# EasyEDA_Source.net
KiCad netlist of a schematic drawn in EasyEDA
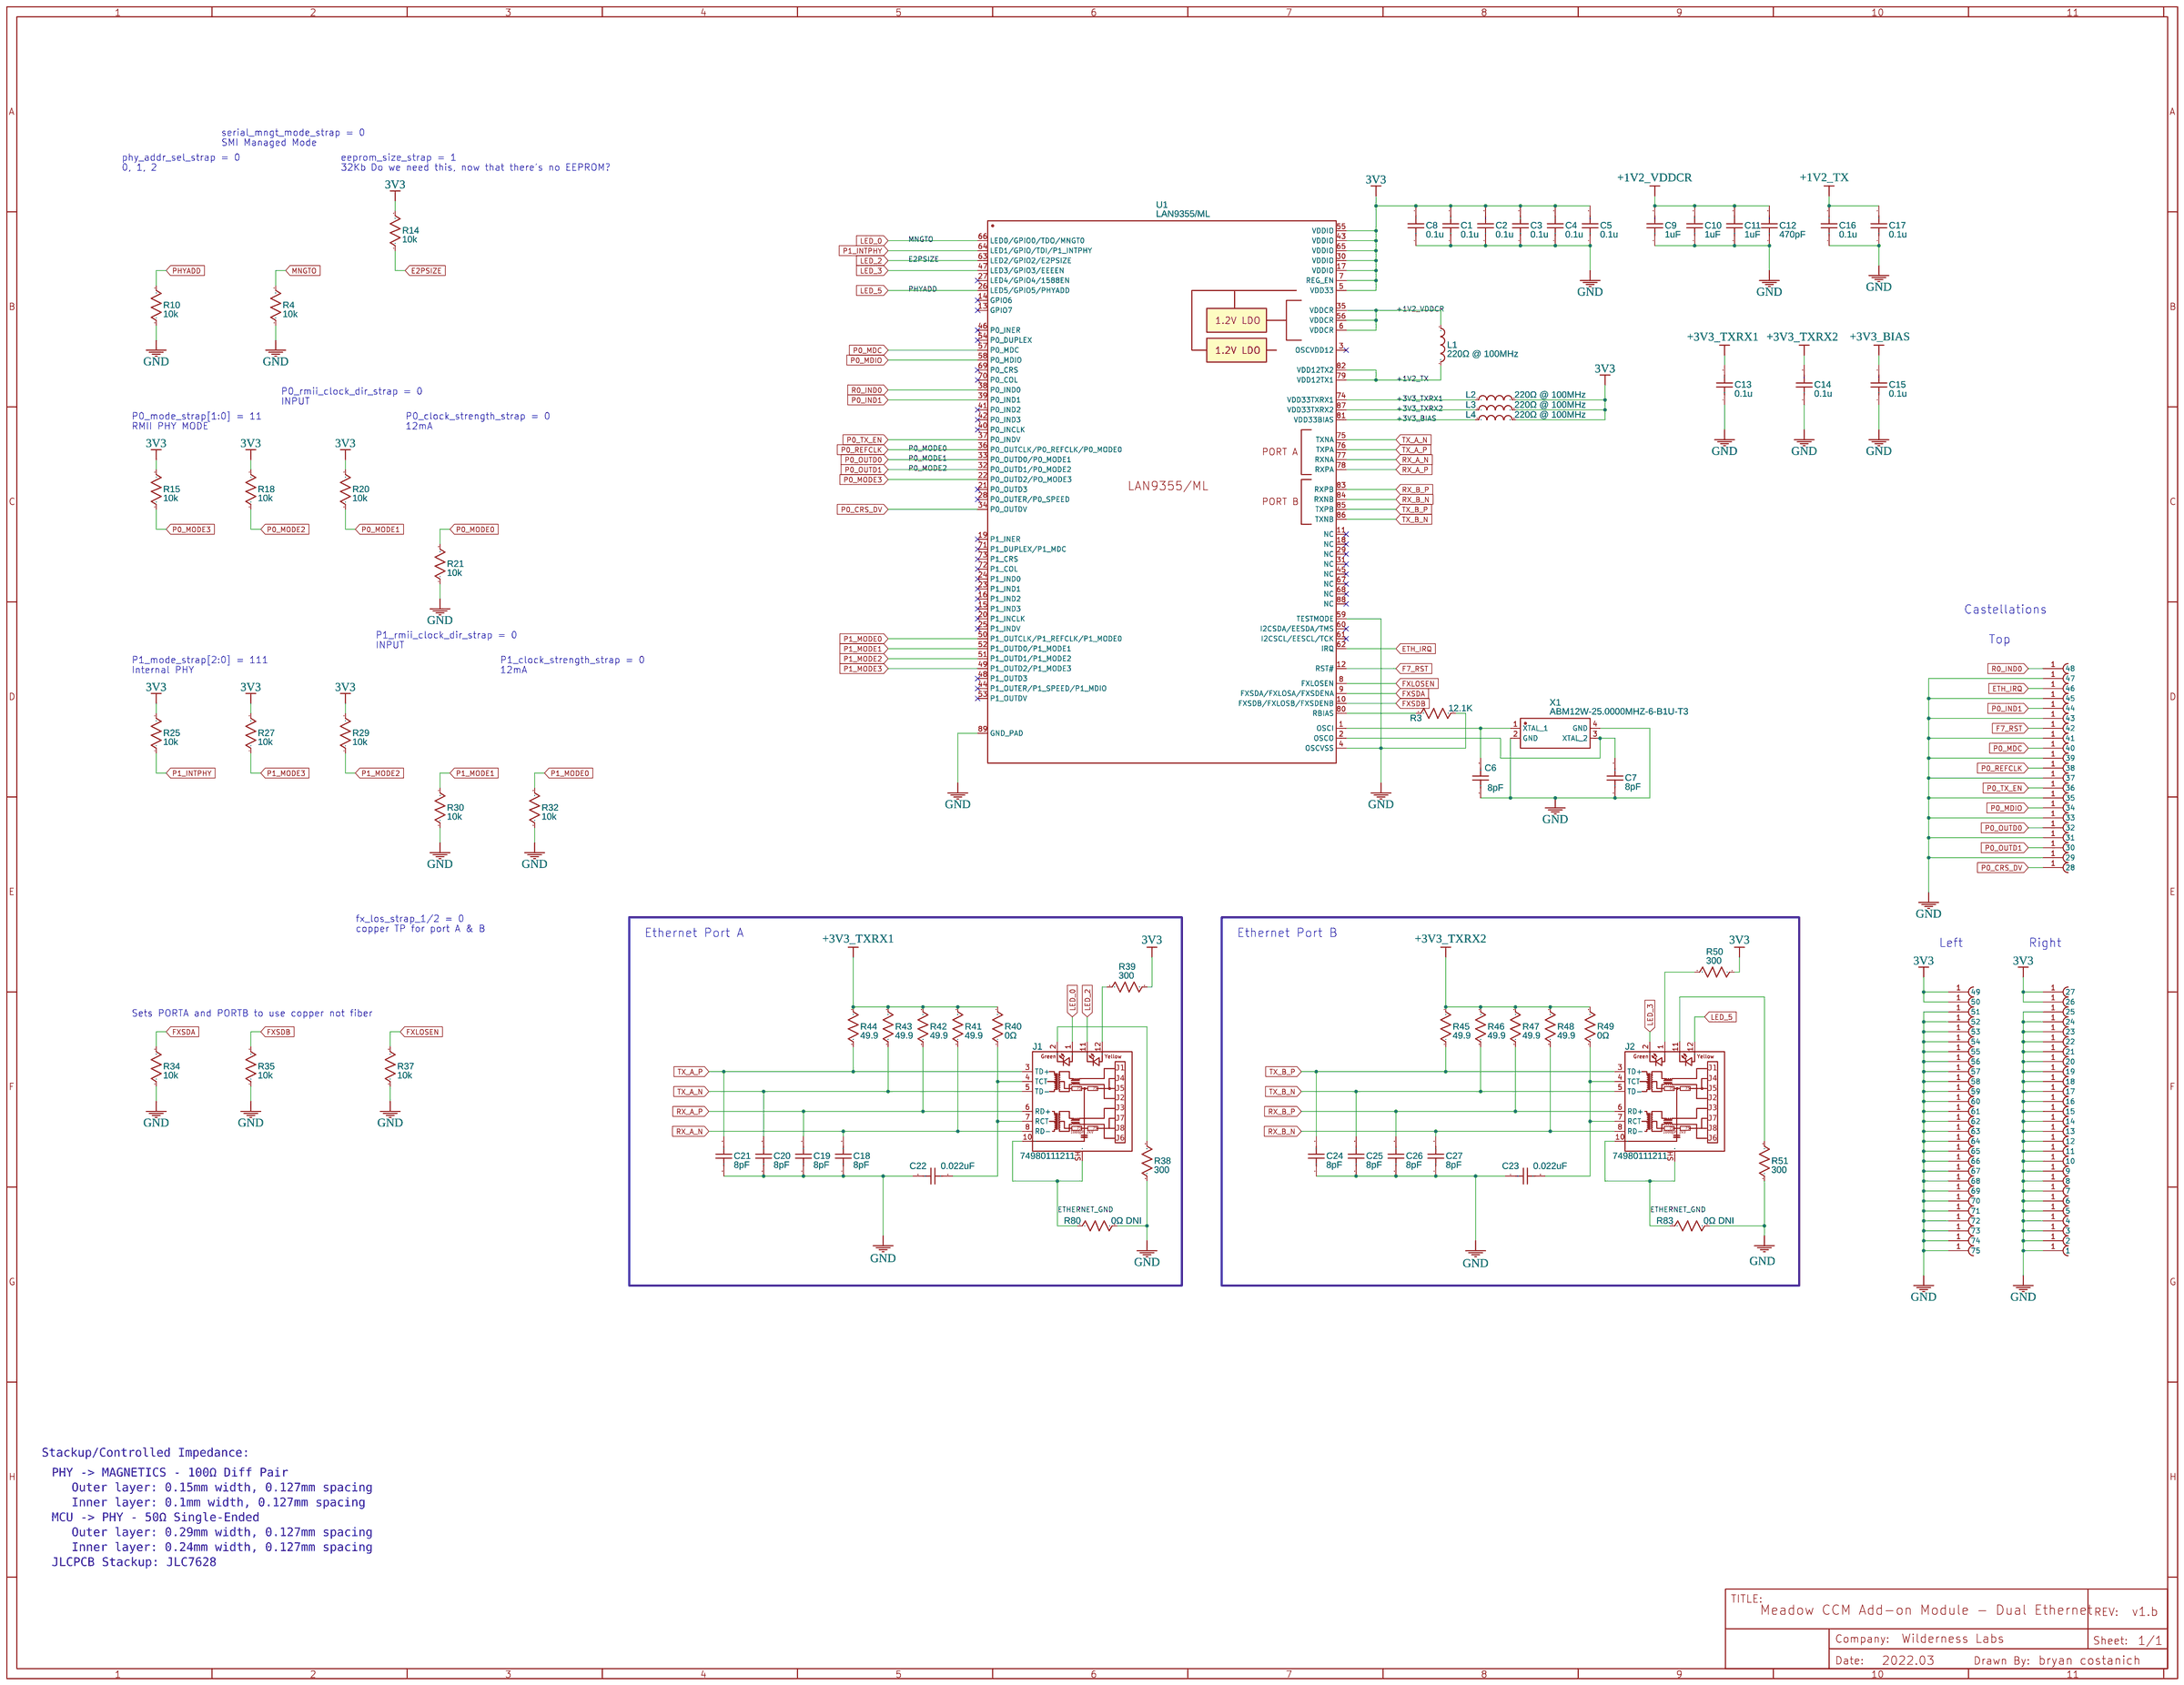
[diagram p0: schematic sheet]

(export (version "E")
  (design (tool "Eeschema 10.0.6"))
  (components
    (comp (ref "C1")
      (value "0.1u")
      (fields (field (name "BOM_Manufacturer Part") "CC0603KRX7R7BB104"))
      (libsource (lib "") (part "C_0603_US"))
    )
    (comp (ref "C2")
      (value "0.1u")
      (fields (field (name "BOM_Manufacturer Part") "CC0603KRX7R7BB104"))
      (libsource (lib "") (part "C_0603_US"))
    )
    (comp (ref "C3")
      (value "0.1u")
      (fields (field (name "BOM_Manufacturer Part") "CC0603KRX7R7BB104"))
      (libsource (lib "") (part "C_0603_US"))
    )
    (comp (ref "C4")
      (value "0.1u")
      (fields (field (name "BOM_Manufacturer Part") "CC0603KRX7R7BB104"))
      (libsource (lib "") (part "C_0603_US"))
    )
    (comp (ref "C5")
      (value "0.1u")
      (fields (field (name "BOM_Manufacturer Part") "CC0603KRX7R7BB104"))
      (libsource (lib "") (part "C_0603_US"))
    )
    (comp (ref "C6")
      (value "8pF")
      (fields (field (name "BOM_Manufacturer Part") "CC0603DRNPO9BN8R0"))
      (libsource (lib "") (part "C_0603_US"))
    )
    (comp (ref "C7")
      (value "8pF")
      (fields (field (name "BOM_Manufacturer Part") "CC0603DRNPO9BN8R0"))
      (libsource (lib "") (part "C_0603_US"))
    )
    (comp (ref "C8")
      (value "0.1u")
      (fields (field (name "BOM_Manufacturer Part") "CC0603KRX7R7BB104"))
      (libsource (lib "") (part "C_0603_US"))
    )
    (comp (ref "C9")
      (value "1uF")
      (fields (field (name "BOM_Manufacturer Part") "CC0603ZRY5V6BB105"))
      (libsource (lib "") (part "C_0603_US"))
    )
    (comp (ref "C10")
      (value "1uF")
      (fields (field (name "BOM_Manufacturer Part") "CC0603ZRY5V6BB105"))
      (libsource (lib "") (part "C_0603_US"))
    )
    (comp (ref "C11")
      (value "1uF")
      (fields (field (name "BOM_Manufacturer Part") "CC0603ZRY5V6BB105"))
      (libsource (lib "") (part "C_0603_US"))
    )
    (comp (ref "C12")
      (value "470pF")
      (fields (field (name "BOM_Manufacturer Part") "CC0603KRX7R9BB471"))
      (libsource (lib "") (part "C_0603_US"))
    )
    (comp (ref "C13")
      (value "0.1u")
      (fields (field (name "BOM_Manufacturer Part") "CC0603KRX7R7BB104"))
      (libsource (lib "") (part "C_0603_US"))
    )
    (comp (ref "C14")
      (value "0.1u")
      (fields (field (name "BOM_Manufacturer Part") "CC0603KRX7R7BB104"))
      (libsource (lib "") (part "C_0603_US"))
    )
    (comp (ref "C15")
      (value "0.1u")
      (fields (field (name "BOM_Manufacturer Part") "CC0603KRX7R7BB104"))
      (libsource (lib "") (part "C_0603_US"))
    )
    (comp (ref "C16")
      (value "0.1u")
      (fields (field (name "BOM_Manufacturer Part") "CC0603KRX7R7BB104"))
      (libsource (lib "") (part "C_0603_US"))
    )
    (comp (ref "C17")
      (value "0.1u")
      (fields (field (name "BOM_Manufacturer Part") "CC0603KRX7R7BB104"))
      (libsource (lib "") (part "C_0603_US"))
    )
    (comp (ref "C18")
      (value "8pF")
      (fields (field (name "BOM_Manufacturer Part") "CC0603DRNPO9BN8R0"))
      (libsource (lib "") (part "C_0603_US"))
    )
    (comp (ref "C19")
      (value "8pF")
      (fields (field (name "BOM_Manufacturer Part") "CC0603DRNPO9BN8R0"))
      (libsource (lib "") (part "C_0603_US"))
    )
    (comp (ref "C20")
      (value "8pF")
      (fields (field (name "BOM_Manufacturer Part") "CC0603DRNPO9BN8R0"))
      (libsource (lib "") (part "C_0603_US"))
    )
    (comp (ref "C21")
      (value "8pF")
      (fields (field (name "BOM_Manufacturer Part") "CC0603DRNPO9BN8R0"))
      (libsource (lib "") (part "C_0603_US"))
    )
    (comp (ref "C22")
      (value "0.022uF")
      (fields (field (name "BOM_Manufacturer Part") "CC0603KRX7R8BB223"))
      (libsource (lib "") (part "C_0603_US_1"))
    )
    (comp (ref "C23")
      (value "0.022uF")
      (fields (field (name "BOM_Manufacturer Part") "CC0603KRX7R8BB223"))
      (libsource (lib "") (part "C_0603_US_1"))
    )
    (comp (ref "C24")
      (value "8pF")
      (fields (field (name "BOM_Manufacturer Part") "CC0603DRNPO9BN8R0"))
      (libsource (lib "") (part "C_0603_US"))
    )
    (comp (ref "C25")
      (value "8pF")
      (fields (field (name "BOM_Manufacturer Part") "CC0603DRNPO9BN8R0"))
      (libsource (lib "") (part "C_0603_US"))
    )
    (comp (ref "C26")
      (value "8pF")
      (fields (field (name "BOM_Manufacturer Part") "CC0603DRNPO9BN8R0"))
      (libsource (lib "") (part "C_0603_US"))
    )
    (comp (ref "C27")
      (value "8pF")
      (fields (field (name "BOM_Manufacturer Part") "CC0603DRNPO9BN8R0"))
      (libsource (lib "") (part "C_0603_US"))
    )
    (comp (ref "J1") (value "74980111211") (libsource (lib "") (part "74980111211")))
    (comp (ref "J2") (value "74980111211") (libsource (lib "") (part "74980111211")))
    (comp (ref "L1")
      (value "220Ω @ 100MHz")
      (fields (field (name "BOM_Manufacturer Part") "BLM18KG221SN1D"))
      (libsource (lib "") (part "L0603_US_1"))
    )
    (comp (ref "L2")
      (value "220Ω @ 100MHz")
      (fields (field (name "BOM_Manufacturer Part") "BLM18KG221SN1D"))
      (libsource (lib "") (part "L0603_US"))
    )
    (comp (ref "L3")
      (value "220Ω @ 100MHz")
      (fields (field (name "BOM_Manufacturer Part") "BLM18KG221SN1D"))
      (libsource (lib "") (part "L0603_US"))
    )
    (comp (ref "L4")
      (value "220Ω @ 100MHz")
      (fields (field (name "BOM_Manufacturer Part") "BLM18KG221SN1D"))
      (libsource (lib "") (part "L0603_US"))
    )
    (comp (ref "R3")
      (value "12.1K")
      (fields (field (name "BOM_Manufacturer Part") "RC0603FR-0712K1L"))
      (libsource (lib "") (part "R_0603_US_1"))
    )
    (comp (ref "R4")
      (value "10k")
      (fields (field (name "BOM_Manufacturer Part") "RC0603FR-0710KL"))
      (libsource (lib "") (part "R_0603_US"))
    )
    (comp (ref "R10")
      (value "10k")
      (fields (field (name "BOM_Manufacturer Part") "RC0603FR-0710KL"))
      (libsource (lib "") (part "R_0603_US"))
    )
    (comp (ref "R14")
      (value "10k")
      (fields (field (name "BOM_Manufacturer Part") "RC0603FR-0710KL"))
      (libsource (lib "") (part "R_0603_US"))
    )
    (comp (ref "R15")
      (value "10k")
      (fields (field (name "BOM_Manufacturer Part") "RC0603FR-0710KL"))
      (libsource (lib "") (part "R_0603_US"))
    )
    (comp (ref "R18")
      (value "10k")
      (fields (field (name "BOM_Manufacturer Part") "RC0603FR-0710KL"))
      (libsource (lib "") (part "R_0603_US"))
    )
    (comp (ref "R20")
      (value "10k")
      (fields (field (name "BOM_Manufacturer Part") "RC0603FR-0710KL"))
      (libsource (lib "") (part "R_0603_US"))
    )
    (comp (ref "R21")
      (value "10k")
      (fields (field (name "BOM_Manufacturer Part") "RC0603FR-0710KL"))
      (libsource (lib "") (part "R_0603_US"))
    )
    (comp (ref "R25")
      (value "10k")
      (fields (field (name "BOM_Manufacturer Part") "RC0603FR-0710KL"))
      (libsource (lib "") (part "R_0603_US"))
    )
    (comp (ref "R27")
      (value "10k")
      (fields (field (name "BOM_Manufacturer Part") "RC0603FR-0710KL"))
      (libsource (lib "") (part "R_0603_US"))
    )
    (comp (ref "R29")
      (value "10k")
      (fields (field (name "BOM_Manufacturer Part") "RC0603FR-0710KL"))
      (libsource (lib "") (part "R_0603_US"))
    )
    (comp (ref "R30")
      (value "10k")
      (fields (field (name "BOM_Manufacturer Part") "RC0603FR-0710KL"))
      (libsource (lib "") (part "R_0603_US"))
    )
    (comp (ref "R32")
      (value "10k")
      (fields (field (name "BOM_Manufacturer Part") "RC0603FR-0710KL"))
      (libsource (lib "") (part "R_0603_US"))
    )
    (comp (ref "R34")
      (value "10k")
      (fields (field (name "BOM_Manufacturer Part") "RC0603FR-0710KL"))
      (libsource (lib "") (part "R_0603_US"))
    )
    (comp (ref "R35")
      (value "10k")
      (fields (field (name "BOM_Manufacturer Part") "RC0603FR-0710KL"))
      (libsource (lib "") (part "R_0603_US"))
    )
    (comp (ref "R37")
      (value "10k")
      (fields (field (name "BOM_Manufacturer Part") "RC0603FR-0710KL"))
      (libsource (lib "") (part "R_0603_US"))
    )
    (comp (ref "R38")
      (value "300")
      (fields (field (name "BOM_Manufacturer Part") "RC0603FR-07300RL"))
      (libsource (lib "") (part "R_0603_US"))
    )
    (comp (ref "R39")
      (value "300")
      (fields (field (name "BOM_Manufacturer Part") "RC0603FR-07300RL"))
      (libsource (lib "") (part "R_0603_US_1"))
    )
    (comp (ref "R40")
      (value "0Ω")
      (fields (field (name "BOM_Manufacturer Part") "RC0603JR-070RL"))
      (libsource (lib "") (part "R_0603_US"))
    )
    (comp (ref "R41")
      (value "49.9")
      (fields (field (name "BOM_Manufacturer Part") "RC0603FR-0749R9L"))
      (libsource (lib "") (part "R_0603_US"))
    )
    (comp (ref "R42")
      (value "49.9")
      (fields (field (name "BOM_Manufacturer Part") "RC0603FR-0749R9L"))
      (libsource (lib "") (part "R_0603_US"))
    )
    (comp (ref "R43")
      (value "49.9")
      (fields (field (name "BOM_Manufacturer Part") "RC0603FR-0749R9L"))
      (libsource (lib "") (part "R_0603_US"))
    )
    (comp (ref "R44")
      (value "49.9")
      (fields (field (name "BOM_Manufacturer Part") "RC0603FR-0749R9L"))
      (libsource (lib "") (part "R_0603_US"))
    )
    (comp (ref "R45")
      (value "49.9")
      (fields (field (name "BOM_Manufacturer Part") "RC0603FR-0749R9L"))
      (libsource (lib "") (part "R_0603_US"))
    )
    (comp (ref "R46")
      (value "49.9")
      (fields (field (name "BOM_Manufacturer Part") "RC0603FR-0749R9L"))
      (libsource (lib "") (part "R_0603_US"))
    )
    (comp (ref "R47")
      (value "49.9")
      (fields (field (name "BOM_Manufacturer Part") "RC0603FR-0749R9L"))
      (libsource (lib "") (part "R_0603_US"))
    )
    (comp (ref "R48")
      (value "49.9")
      (fields (field (name "BOM_Manufacturer Part") "RC0603FR-0749R9L"))
      (libsource (lib "") (part "R_0603_US"))
    )
    (comp (ref "R49")
      (value "0Ω")
      (fields (field (name "BOM_Manufacturer Part") "RC0603JR-070RL"))
      (libsource (lib "") (part "R_0603_US"))
    )
    (comp (ref "R50")
      (value "300")
      (fields (field (name "BOM_Manufacturer Part") "RC0603FR-07300RL"))
      (libsource (lib "") (part "R_0603_US_1"))
    )
    (comp (ref "R51")
      (value "300")
      (fields (field (name "BOM_Manufacturer Part") "RC0603FR-07300RL"))
      (libsource (lib "") (part "R_0603_US"))
    )
    (comp (ref "R80")
      (value "0Ω DNI")
      (fields (field (name "BOM_Manufacturer Part") "RC0603JR-070RL"))
      (libsource (lib "") (part "R_0603_US_2"))
    )
    (comp (ref "R83")
      (value "0Ω DNI")
      (fields (field (name "BOM_Manufacturer Part") "RC0603JR-070RL"))
      (libsource (lib "") (part "R_0603_US_2"))
    )
    (comp (ref "U1")
      (value "LAN9355/ML")
      (fields (field (name "BOM_Manufacturer Part") "LAN9355I/ML"))
      (libsource (lib "") (part "LAN9355/ML"))
    )
    (comp (ref "U2") (value "1.2MM SMT Castellation") (libsource (lib "") (part "1.2MM SMT Castellation_69")))
    (comp (ref "U3") (value "1.2MM SMT Castellation") (libsource (lib "") (part "1.2MM SMT Castellation_27")))
    (comp (ref "U4") (value "1.2MM SMT Castellation") (libsource (lib "") (part "1.2MM SMT Castellation_32")))
    (comp (ref "U5") (value "1.2MM SMT Castellation") (libsource (lib "") (part "1.2MM SMT Castellation_5")))
    (comp (ref "U6") (value "1.2MM SMT Castellation") (libsource (lib "") (part "1.2MM SMT Castellation_40")))
    (comp (ref "U7") (value "1.2MM SMT Castellation") (libsource (lib "") (part "1.2MM SMT Castellation_8")))
    (comp (ref "U8") (value "1.2MM SMT Castellation") (libsource (lib "") (part "1.2MM SMT Castellation_25")))
    (comp (ref "U9") (value "1.2MM SMT Castellation") (libsource (lib "") (part "1.2MM SMT Castellation_70")))
    (comp (ref "U10")
      (value "1.2MM SMT Castellation")
      (libsource (lib "") (part "1.2MM SMT Castellation_12"))
    )
    (comp (ref "U11")
      (value "1.2MM SMT Castellation")
      (libsource (lib "") (part "1.2MM SMT Castellation_68"))
    )
    (comp (ref "U12")
      (value "WILDERNESS_LABS_LOGO_HORIZONTAL_MEDIUM")
      (libsource (lib "") (part "WILDERNESS_LABS_LOGO_HORIZONTAL_MEDIUM"))
    )
    (comp (ref "U13")
      (value "1.2MM SMT Castellation")
      (libsource (lib "") (part "1.2MM SMT Castellation_34"))
    )
    (comp (ref "U14") (value "1.2MM SMT Castellation") (libsource (lib "") (part "1.2MM SMT Castellation_6")))
    (comp (ref "U15")
      (value "1.2MM SMT Castellation")
      (libsource (lib "") (part "1.2MM SMT Castellation_21"))
    )
    (comp (ref "U16")
      (value "1.2MM SMT Castellation")
      (libsource (lib "") (part "1.2MM SMT Castellation_43"))
    )
    (comp (ref "U17")
      (value "1.2MM SMT Castellation")
      (libsource (lib "") (part "1.2MM SMT Castellation_30"))
    )
    (comp (ref "U18")
      (value "1.2MM SMT Castellation")
      (libsource (lib "") (part "1.2MM SMT Castellation_41"))
    )
    (comp (ref "U19")
      (value "1.2MM SMT Castellation")
      (libsource (lib "") (part "1.2MM SMT Castellation_10"))
    )
    (comp (ref "U20")
      (value "1.2MM SMT Castellation")
      (libsource (lib "") (part "1.2MM SMT Castellation_19"))
    )
    (comp (ref "U21")
      (value "1.2MM SMT Castellation")
      (libsource (lib "") (part "1.2MM SMT Castellation_37"))
    )
    (comp (ref "U22")
      (value "1.2MM SMT Castellation")
      (libsource (lib "") (part "1.2MM SMT Castellation_42"))
    )
    (comp (ref "U23")
      (value "1.2MM SMT Castellation")
      (libsource (lib "") (part "1.2MM SMT Castellation_11"))
    )
    (comp (ref "U24")
      (value "1.2MM SMT Castellation")
      (libsource (lib "") (part "1.2MM SMT Castellation_60"))
    )
    (comp (ref "U25")
      (value "1.2MM SMT Castellation")
      (libsource (lib "") (part "1.2MM SMT Castellation_46"))
    )
    (comp (ref "U26")
      (value "1.2MM SMT Castellation")
      (libsource (lib "") (part "1.2MM SMT Castellation_57"))
    )
    (comp (ref "U27")
      (value "1.2MM SMT Castellation")
      (libsource (lib "") (part "1.2MM SMT Castellation_63"))
    )
    (comp (ref "U28")
      (value "1.2MM SMT Castellation")
      (libsource (lib "") (part "1.2MM SMT Castellation_38"))
    )
    (comp (ref "U29")
      (value "1.2MM SMT Castellation")
      (libsource (lib "") (part "1.2MM SMT Castellation_48"))
    )
    (comp (ref "U30")
      (value "1.2MM SMT Castellation")
      (libsource (lib "") (part "1.2MM SMT Castellation_62"))
    )
    (comp (ref "U31")
      (value "1.2MM SMT Castellation")
      (libsource (lib "") (part "1.2MM SMT Castellation_23"))
    )
    (comp (ref "U32")
      (value "1.2MM SMT Castellation")
      (libsource (lib "") (part "1.2MM SMT Castellation_55"))
    )
    (comp (ref "U33")
      (value "1.2MM SMT Castellation")
      (libsource (lib "") (part "1.2MM SMT Castellation_65"))
    )
    (comp (ref "U34")
      (value "1.2MM SMT Castellation")
      (libsource (lib "") (part "1.2MM SMT Castellation_67"))
    )
    (comp (ref "U35")
      (value "1.2MM SMT Castellation")
      (libsource (lib "") (part "1.2MM SMT Castellation_72"))
    )
    (comp (ref "U36")
      (value "1.2MM SMT Castellation")
      (libsource (lib "") (part "1.2MM SMT Castellation_47"))
    )
    (comp (ref "U37")
      (value "1.2MM SMT Castellation")
      (libsource (lib "") (part "1.2MM SMT Castellation_20"))
    )
    (comp (ref "U38")
      (value "1.2MM SMT Castellation")
      (libsource (lib "") (part "1.2MM SMT Castellation_51"))
    )
    (comp (ref "U39")
      (value "1.2MM SMT Castellation")
      (libsource (lib "") (part "1.2MM SMT Castellation_24"))
    )
    (comp (ref "U40")
      (value "1.2MM SMT Castellation")
      (libsource (lib "") (part "1.2MM SMT Castellation_56"))
    )
    (comp (ref "U41")
      (value "1.2MM SMT Castellation")
      (libsource (lib "") (part "1.2MM SMT Castellation_36"))
    )
    (comp (ref "U42")
      (value "1.2MM SMT Castellation")
      (libsource (lib "") (part "1.2MM SMT Castellation_22"))
    )
    (comp (ref "U43")
      (value "1.2MM SMT Castellation")
      (libsource (lib "") (part "1.2MM SMT Castellation_73"))
    )
    (comp (ref "U44")
      (value "1.2MM SMT Castellation")
      (libsource (lib "") (part "1.2MM SMT Castellation_39"))
    )
    (comp (ref "U45")
      (value "1.2MM SMT Castellation")
      (libsource (lib "") (part "1.2MM SMT Castellation_52"))
    )
    (comp (ref "U46")
      (value "1.2MM SMT Castellation")
      (libsource (lib "") (part "1.2MM SMT Castellation_33"))
    )
    (comp (ref "U47") (value "1.2MM SMT Castellation") (libsource (lib "") (part "1.2MM SMT Castellation")))
    (comp (ref "U48")
      (value "1.2MM SMT Castellation")
      (libsource (lib "") (part "1.2MM SMT Castellation_18"))
    )
    (comp (ref "U49")
      (value "1.2MM SMT Castellation")
      (libsource (lib "") (part "1.2MM SMT Castellation_50"))
    )
    (comp (ref "U50")
      (value "1.2MM SMT Castellation")
      (libsource (lib "") (part "1.2MM SMT Castellation_49"))
    )
    (comp (ref "U51")
      (value "1.2MM SMT Castellation")
      (libsource (lib "") (part "1.2MM SMT Castellation_15"))
    )
    (comp (ref "U52")
      (value "1.2MM SMT Castellation")
      (libsource (lib "") (part "1.2MM SMT Castellation_64"))
    )
    (comp (ref "U53") (value "1.2MM SMT Castellation") (libsource (lib "") (part "1.2MM SMT Castellation_7")))
    (comp (ref "U54")
      (value "1.2MM SMT Castellation")
      (libsource (lib "") (part "1.2MM SMT Castellation_61"))
    )
    (comp (ref "U55")
      (value "1.2MM SMT Castellation")
      (libsource (lib "") (part "1.2MM SMT Castellation_45"))
    )
    (comp (ref "U56")
      (value "1.2MM SMT Castellation")
      (libsource (lib "") (part "1.2MM SMT Castellation_54"))
    )
    (comp (ref "U57")
      (value "1.2MM SMT Castellation")
      (libsource (lib "") (part "1.2MM SMT Castellation_17"))
    )
    (comp (ref "U58")
      (value "1.2MM SMT Castellation")
      (libsource (lib "") (part "1.2MM SMT Castellation_35"))
    )
    (comp (ref "U59")
      (value "1.2MM SMT Castellation")
      (libsource (lib "") (part "1.2MM SMT Castellation_28"))
    )
    (comp (ref "U60")
      (value "1.2MM SMT Castellation")
      (libsource (lib "") (part "1.2MM SMT Castellation_44"))
    )
    (comp (ref "U61")
      (value "1.2MM SMT Castellation")
      (libsource (lib "") (part "1.2MM SMT Castellation_29"))
    )
    (comp (ref "U62")
      (value "1.2MM SMT Castellation")
      (libsource (lib "") (part "1.2MM SMT Castellation_71"))
    )
    (comp (ref "U63")
      (value "1.2MM SMT Castellation")
      (libsource (lib "") (part "1.2MM SMT Castellation_16"))
    )
    (comp (ref "U64")
      (value "1.2MM SMT Castellation")
      (libsource (lib "") (part "1.2MM SMT Castellation_59"))
    )
    (comp (ref "U65") (value "1.2MM SMT Castellation") (libsource (lib "") (part "1.2MM SMT Castellation_3")))
    (comp (ref "U66")
      (value "1.2MM SMT Castellation")
      (libsource (lib "") (part "1.2MM SMT Castellation_26"))
    )
    (comp (ref "U67")
      (value "1.2MM SMT Castellation")
      (libsource (lib "") (part "1.2MM SMT Castellation_58"))
    )
    (comp (ref "U68")
      (value "1.2MM SMT Castellation")
      (libsource (lib "") (part "1.2MM SMT Castellation_13"))
    )
    (comp (ref "U69")
      (value "1.2MM SMT Castellation")
      (libsource (lib "") (part "1.2MM SMT Castellation_66"))
    )
    (comp (ref "U70")
      (value "1.2MM SMT Castellation")
      (libsource (lib "") (part "1.2MM SMT Castellation_53"))
    )
    (comp (ref "U71") (value "1.2MM SMT Castellation") (libsource (lib "") (part "1.2MM SMT Castellation_2")))
    (comp (ref "U72")
      (value "1.2MM SMT Castellation")
      (libsource (lib "") (part "1.2MM SMT Castellation_74"))
    )
    (comp (ref "U73") (value "1.2MM SMT Castellation") (libsource (lib "") (part "1.2MM SMT Castellation_9")))
    (comp (ref "U74")
      (value "1.2MM SMT Castellation")
      (libsource (lib "") (part "1.2MM SMT Castellation_14"))
    )
    (comp (ref "U75") (value "1.2MM SMT Castellation") (libsource (lib "") (part "1.2MM SMT Castellation_4")))
    (comp (ref "U76") (value "1.2MM SMT Castellation") (libsource (lib "") (part "1.2MM SMT Castellation_1")))
    (comp (ref "U78")
      (value "1.2MM SMT Castellation")
      (libsource (lib "") (part "1.2MM SMT Castellation_31"))
    )
    (comp (ref "X1")
      (value "ABM12W-25.0000MHZ-6-B1U-T3")
      (libsource (lib "") (part "ABM12W-25.0000MHZ-6-B1U-T3"))
    )
  )
  (nets
    (net (code "1") (name "+1V2_TX") (class "Default")
      (node (ref "C16") (pin "2") (pinfunction "2_2") (pintype "unspecified"))
      (node (ref "C17") (pin "2") (pinfunction "2_2") (pintype "unspecified"))
      (node (ref "L1") (pin "2") (pinfunction "2_2") (pintype "unspecified"))
      (node (ref "U1") (pin "79") (pinfunction "VDD12TX1_79") (pintype "unspecified"))
      (node (ref "U1") (pin "82") (pinfunction "VDD12TX2_82") (pintype "unspecified"))
    )
    (net (code "2") (name "+1V2_VDDCR") (class "Default")
      (node (ref "C10") (pin "2") (pinfunction "2_2") (pintype "unspecified"))
      (node (ref "C11") (pin "2") (pinfunction "2_2") (pintype "unspecified"))
      (node (ref "C12") (pin "2") (pinfunction "2_2") (pintype "unspecified"))
      (node (ref "C9") (pin "2") (pinfunction "2_2") (pintype "unspecified"))
      (node (ref "L1") (pin "1") (pinfunction "1_1") (pintype "unspecified"))
      (node (ref "U1") (pin "35") (pinfunction "VDDCR_35") (pintype "unspecified"))
      (node (ref "U1") (pin "56") (pinfunction "VDDCR_56") (pintype "unspecified"))
      (node (ref "U1") (pin "6") (pinfunction "VDDCR_6") (pintype "unspecified"))
    )
    (net (code "3") (name "+3V3_BIAS") (class "Default")
      (node (ref "C15") (pin "2") (pinfunction "2_2") (pintype "unspecified"))
      (node (ref "L4") (pin "1") (pinfunction "1_1") (pintype "unspecified"))
      (node (ref "U1") (pin "81") (pinfunction "VDD33BIAS_81") (pintype "unspecified"))
    )
    (net (code "4") (name "+3V3_TXRX1") (class "Default")
      (node (ref "C13") (pin "2") (pinfunction "2_2") (pintype "unspecified"))
      (node (ref "L2") (pin "1") (pinfunction "1_1") (pintype "unspecified"))
      (node (ref "R40") (pin "2") (pinfunction "2_2") (pintype "unspecified"))
      (node (ref "R41") (pin "2") (pinfunction "2_2") (pintype "unspecified"))
      (node (ref "R42") (pin "2") (pinfunction "2_2") (pintype "unspecified"))
      (node (ref "R43") (pin "2") (pinfunction "2_2") (pintype "unspecified"))
      (node (ref "R44") (pin "2") (pinfunction "2_2") (pintype "unspecified"))
      (node (ref "U1") (pin "74") (pinfunction "VDD33TXRX1_74") (pintype "unspecified"))
    )
    (net (code "5") (name "+3V3_TXRX2") (class "Default")
      (node (ref "C14") (pin "2") (pinfunction "2_2") (pintype "unspecified"))
      (node (ref "L3") (pin "1") (pinfunction "1_1") (pintype "unspecified"))
      (node (ref "R45") (pin "2") (pinfunction "2_2") (pintype "unspecified"))
      (node (ref "R46") (pin "2") (pinfunction "2_2") (pintype "unspecified"))
      (node (ref "R47") (pin "2") (pinfunction "2_2") (pintype "unspecified"))
      (node (ref "R48") (pin "2") (pinfunction "2_2") (pintype "unspecified"))
      (node (ref "R49") (pin "2") (pinfunction "2_2") (pintype "unspecified"))
      (node (ref "U1") (pin "87") (pinfunction "VDD33TXRX2_87") (pintype "unspecified"))
    )
    (net (code "6") (name "/ETHERNET_GND") (class "Default")
      (node (ref "J1") (pin "10") (pinfunction "CHS_10") (pintype "unspecified"))
      (node (ref "J1") (pin "SH") (pinfunction "SH_SH") (pintype "unspecified"))
      (node (ref "J2") (pin "10") (pinfunction "CHS_10") (pintype "unspecified"))
      (node (ref "J2") (pin "SH") (pinfunction "SH_SH") (pintype "unspecified"))
      (node (ref "R80") (pin "1") (pinfunction "1_1") (pintype "unspecified"))
      (node (ref "R83") (pin "1") (pinfunction "1_1") (pintype "unspecified"))
    )
    (net (code "7") (name "3V3") (class "Default")
      (node (ref "C1") (pin "2") (pinfunction "2_2") (pintype "unspecified"))
      (node (ref "C2") (pin "2") (pinfunction "2_2") (pintype "unspecified"))
      (node (ref "C3") (pin "2") (pinfunction "2_2") (pintype "unspecified"))
      (node (ref "C4") (pin "2") (pinfunction "2_2") (pintype "unspecified"))
      (node (ref "C5") (pin "2") (pinfunction "2_2") (pintype "unspecified"))
      (node (ref "C8") (pin "2") (pinfunction "2_2") (pintype "unspecified"))
      (node (ref "L2") (pin "2") (pinfunction "2_2") (pintype "unspecified"))
      (node (ref "L3") (pin "2") (pinfunction "2_2") (pintype "unspecified"))
      (node (ref "L4") (pin "2") (pinfunction "2_2") (pintype "unspecified"))
      (node (ref "R14") (pin "2") (pinfunction "2_2") (pintype "unspecified"))
      (node (ref "R15") (pin "2") (pinfunction "2_2") (pintype "unspecified"))
      (node (ref "R18") (pin "2") (pinfunction "2_2") (pintype "unspecified"))
      (node (ref "R20") (pin "2") (pinfunction "2_2") (pintype "unspecified"))
      (node (ref "R25") (pin "2") (pinfunction "2_2") (pintype "unspecified"))
      (node (ref "R27") (pin "2") (pinfunction "2_2") (pintype "unspecified"))
      (node (ref "R29") (pin "2") (pinfunction "2_2") (pintype "unspecified"))
      (node (ref "R39") (pin "1") (pinfunction "1_1") (pintype "unspecified"))
      (node (ref "R50") (pin "1") (pinfunction "1_1") (pintype "unspecified"))
      (node (ref "U1") (pin "17") (pinfunction "VDDIO_17") (pintype "unspecified"))
      (node (ref "U1") (pin "30") (pinfunction "VDDIO_30") (pintype "unspecified"))
      (node (ref "U1") (pin "43") (pinfunction "VDDIO_43") (pintype "unspecified"))
      (node (ref "U1") (pin "5") (pinfunction "VDD33_5") (pintype "unspecified"))
      (node (ref "U1") (pin "55") (pinfunction "VDDIO_55") (pintype "unspecified"))
      (node (ref "U1") (pin "65") (pinfunction "VDDIO_65") (pintype "unspecified"))
      (node (ref "U1") (pin "7") (pinfunction "REG_EN_7") (pintype "unspecified"))
      (node (ref "U13") (pin "1") (pinfunction "50_1") (pintype "unspecified"))
      (node (ref "U50") (pin "1") (pinfunction "26_1") (pintype "unspecified"))
      (node (ref "U53") (pin "1") (pinfunction "49_1") (pintype "unspecified"))
      (node (ref "U71") (pin "1") (pinfunction "27_1") (pintype "unspecified"))
    )
    (net (code "8") (name "E2PSIZE") (class "Default")
      (node (ref "J1") (pin "11") (pinfunction "11_11") (pintype "unspecified"))
      (node (ref "R14") (pin "1") (pinfunction "1_1") (pintype "unspecified"))
      (node (ref "U1") (pin "63") (pinfunction "LED2/GPIO2/E2PSIZE_63") (pintype "unspecified"))
    )
    (net (code "9") (name "ETH_IRQ") (class "Default")
      (node (ref "U1") (pin "62") (pinfunction "IRQ_62") (pintype "unspecified"))
      (node (ref "U67") (pin "1") (pinfunction "46_1") (pintype "unspecified"))
    )
    (net (code "10") (name "F7_RST") (class "Default")
      (node (ref "U1") (pin "12") (pinfunction "RST#_12") (pintype "unspecified"))
      (node (ref "U45") (pin "1") (pinfunction "42_1") (pintype "unspecified"))
    )
    (net (code "11") (name "FXLOSEN") (class "Default")
      (node (ref "R37") (pin "2") (pinfunction "2_2") (pintype "unspecified"))
      (node (ref "U1") (pin "8") (pinfunction "FXLOSEN_8") (pintype "unspecified"))
    )
    (net (code "12") (name "FXSDA") (class "Default")
      (node (ref "R34") (pin "2") (pinfunction "2_2") (pintype "unspecified"))
      (node (ref "U1") (pin "9") (pinfunction "FXSDA/FXLOSA/FXSDENA_9") (pintype "unspecified"))
    )
    (net (code "13") (name "FXSDB") (class "Default")
      (node (ref "R35") (pin "2") (pinfunction "2_2") (pintype "unspecified"))
      (node (ref "U1") (pin "10") (pinfunction "FXSDB/FXLOSB/FXSDENB_10") (pintype "unspecified"))
    )
    (net (code "14") (name "GND") (class "Default")
      (node (ref "C1") (pin "1") (pinfunction "1_1") (pintype "unspecified"))
      (node (ref "C10") (pin "1") (pinfunction "1_1") (pintype "unspecified"))
      (node (ref "C11") (pin "1") (pinfunction "1_1") (pintype "unspecified"))
      (node (ref "C12") (pin "1") (pinfunction "1_1") (pintype "unspecified"))
      (node (ref "C13") (pin "1") (pinfunction "1_1") (pintype "unspecified"))
      (node (ref "C14") (pin "1") (pinfunction "1_1") (pintype "unspecified"))
      (node (ref "C15") (pin "1") (pinfunction "1_1") (pintype "unspecified"))
      (node (ref "C16") (pin "1") (pinfunction "1_1") (pintype "unspecified"))
      (node (ref "C17") (pin "1") (pinfunction "1_1") (pintype "unspecified"))
      (node (ref "C18") (pin "1") (pinfunction "1_1") (pintype "unspecified"))
      (node (ref "C19") (pin "1") (pinfunction "1_1") (pintype "unspecified"))
      (node (ref "C2") (pin "1") (pinfunction "1_1") (pintype "unspecified"))
      (node (ref "C20") (pin "1") (pinfunction "1_1") (pintype "unspecified"))
      (node (ref "C21") (pin "1") (pinfunction "1_1") (pintype "unspecified"))
      (node (ref "C22") (pin "1") (pinfunction "1_1") (pintype "unspecified"))
      (node (ref "C23") (pin "1") (pinfunction "1_1") (pintype "unspecified"))
      (node (ref "C24") (pin "1") (pinfunction "1_1") (pintype "unspecified"))
      (node (ref "C25") (pin "1") (pinfunction "1_1") (pintype "unspecified"))
      (node (ref "C26") (pin "1") (pinfunction "1_1") (pintype "unspecified"))
      (node (ref "C27") (pin "1") (pinfunction "1_1") (pintype "unspecified"))
      (node (ref "C3") (pin "1") (pinfunction "1_1") (pintype "unspecified"))
      (node (ref "C4") (pin "1") (pinfunction "1_1") (pintype "unspecified"))
      (node (ref "C5") (pin "1") (pinfunction "1_1") (pintype "unspecified"))
      (node (ref "C6") (pin "1") (pinfunction "1_1") (pintype "unspecified"))
      (node (ref "C7") (pin "1") (pinfunction "1_1") (pintype "unspecified"))
      (node (ref "C8") (pin "1") (pinfunction "1_1") (pintype "unspecified"))
      (node (ref "C9") (pin "1") (pinfunction "1_1") (pintype "unspecified"))
      (node (ref "R10") (pin "1") (pinfunction "1_1") (pintype "unspecified"))
      (node (ref "R21") (pin "1") (pinfunction "1_1") (pintype "unspecified"))
      (node (ref "R3") (pin "1") (pinfunction "1_1") (pintype "unspecified"))
      (node (ref "R30") (pin "1") (pinfunction "1_1") (pintype "unspecified"))
      (node (ref "R32") (pin "1") (pinfunction "1_1") (pintype "unspecified"))
      (node (ref "R34") (pin "1") (pinfunction "1_1") (pintype "unspecified"))
      (node (ref "R35") (pin "1") (pinfunction "1_1") (pintype "unspecified"))
      (node (ref "R37") (pin "1") (pinfunction "1_1") (pintype "unspecified"))
      (node (ref "R38") (pin "1") (pinfunction "1_1") (pintype "unspecified"))
      (node (ref "R4") (pin "1") (pinfunction "1_1") (pintype "unspecified"))
      (node (ref "R51") (pin "1") (pinfunction "1_1") (pintype "unspecified"))
      (node (ref "R80") (pin "2") (pinfunction "2_2") (pintype "unspecified"))
      (node (ref "R83") (pin "2") (pinfunction "2_2") (pintype "unspecified"))
      (node (ref "U1") (pin "4") (pinfunction "OSCVSS_4") (pintype "unspecified"))
      (node (ref "U1") (pin "59") (pinfunction "TESTMODE_59") (pintype "unspecified"))
      (node (ref "U1") (pin "89") (pinfunction "GND_PAD_89") (pintype "unspecified"))
      (node (ref "U11") (pin "1") (pinfunction "37_1") (pintype "unspecified"))
      (node (ref "U14") (pin "1") (pinfunction "51_1") (pintype "unspecified"))
      (node (ref "U15") (pin "1") (pinfunction "2_1") (pintype "unspecified"))
      (node (ref "U16") (pin "1") (pinfunction "52_1") (pintype "unspecified"))
      (node (ref "U17") (pin "1") (pinfunction "3_1") (pintype "unspecified"))
      (node (ref "U18") (pin "1") (pinfunction "4_1") (pintype "unspecified"))
      (node (ref "U19") (pin "1") (pinfunction "53_1") (pintype "unspecified"))
      (node (ref "U21") (pin "1") (pinfunction "5_1") (pintype "unspecified"))
      (node (ref "U22") (pin "1") (pinfunction "6_1") (pintype "unspecified"))
      (node (ref "U23") (pin "1") (pinfunction "54_1") (pintype "unspecified"))
      (node (ref "U24") (pin "1") (pinfunction "39_1") (pintype "unspecified"))
      (node (ref "U25") (pin "1") (pinfunction "7_1") (pintype "unspecified"))
      (node (ref "U27") (pin "1") (pinfunction "8_1") (pintype "unspecified"))
      (node (ref "U28") (pin "1") (pinfunction "9_1") (pintype "unspecified"))
      (node (ref "U29") (pin "1") (pinfunction "10_1") (pintype "unspecified"))
      (node (ref "U3") (pin "1") (pinfunction "29_1") (pintype "unspecified"))
      (node (ref "U30") (pin "1") (pinfunction "41_1") (pintype "unspecified"))
      (node (ref "U31") (pin "1") (pinfunction "11_1") (pintype "unspecified"))
      (node (ref "U32") (pin "1") (pinfunction "12_1") (pintype "unspecified"))
      (node (ref "U33") (pin "1") (pinfunction "13_1") (pintype "unspecified"))
      (node (ref "U34") (pin "1") (pinfunction "14_1") (pintype "unspecified"))
      (node (ref "U35") (pin "1") (pinfunction "15_1") (pintype "unspecified"))
      (node (ref "U36") (pin "1") (pinfunction "16_1") (pintype "unspecified"))
      (node (ref "U37") (pin "1") (pinfunction "17_1") (pintype "unspecified"))
      (node (ref "U38") (pin "1") (pinfunction "18_1") (pintype "unspecified"))
      (node (ref "U39") (pin "1") (pinfunction "19_1") (pintype "unspecified"))
      (node (ref "U40") (pin "1") (pinfunction "20_1") (pintype "unspecified"))
      (node (ref "U41") (pin "1") (pinfunction "55_1") (pintype "unspecified"))
      (node (ref "U42") (pin "1") (pinfunction "21_1") (pintype "unspecified"))
      (node (ref "U43") (pin "1") (pinfunction "22_1") (pintype "unspecified"))
      (node (ref "U44") (pin "1") (pinfunction "23_1") (pintype "unspecified"))
      (node (ref "U46") (pin "1") (pinfunction "43_1") (pintype "unspecified"))
      (node (ref "U48") (pin "1") (pinfunction "24_1") (pintype "unspecified"))
      (node (ref "U49") (pin "1") (pinfunction "25_1") (pintype "unspecified"))
      (node (ref "U5") (pin "1") (pinfunction "31_1") (pintype "unspecified"))
      (node (ref "U51") (pin "1") (pinfunction "56_1") (pintype "unspecified"))
      (node (ref "U52") (pin "1") (pinfunction "57_1") (pintype "unspecified"))
      (node (ref "U54") (pin "1") (pinfunction "58_1") (pintype "unspecified"))
      (node (ref "U55") (pin "1") (pinfunction "59_1") (pintype "unspecified"))
      (node (ref "U56") (pin "1") (pinfunction "60_1") (pintype "unspecified"))
      (node (ref "U57") (pin "1") (pinfunction "45_1") (pintype "unspecified"))
      (node (ref "U58") (pin "1") (pinfunction "61_1") (pintype "unspecified"))
      (node (ref "U59") (pin "1") (pinfunction "62_1") (pintype "unspecified"))
      (node (ref "U60") (pin "1") (pinfunction "63_1") (pintype "unspecified"))
      (node (ref "U61") (pin "1") (pinfunction "64_1") (pintype "unspecified"))
      (node (ref "U62") (pin "1") (pinfunction "65_1") (pintype "unspecified"))
      (node (ref "U63") (pin "1") (pinfunction "66_1") (pintype "unspecified"))
      (node (ref "U64") (pin "1") (pinfunction "67_1") (pintype "unspecified"))
      (node (ref "U65") (pin "1") (pinfunction "68_1") (pintype "unspecified"))
      (node (ref "U66") (pin "1") (pinfunction "69_1") (pintype "unspecified"))
      (node (ref "U68") (pin "1") (pinfunction "70_1") (pintype "unspecified"))
      (node (ref "U69") (pin "1") (pinfunction "71_1") (pintype "unspecified"))
      (node (ref "U7") (pin "1") (pinfunction "33_1") (pintype "unspecified"))
      (node (ref "U70") (pin "1") (pinfunction "72_1") (pintype "unspecified"))
      (node (ref "U72") (pin "1") (pinfunction "73_1") (pintype "unspecified"))
      (node (ref "U73") (pin "1") (pinfunction "74_1") (pintype "unspecified"))
      (node (ref "U74") (pin "1") (pinfunction "47_1") (pintype "unspecified"))
      (node (ref "U75") (pin "1") (pinfunction "75_1") (pintype "unspecified"))
      (node (ref "U78") (pin "1") (pinfunction "1_1") (pintype "unspecified"))
      (node (ref "U9") (pin "1") (pinfunction "35_1") (pintype "unspecified"))
      (node (ref "X1") (pin "2") (pinfunction "GND_2") (pintype "unspecified"))
      (node (ref "X1") (pin "4") (pinfunction "GND_4") (pintype "unspecified"))
    )
    (net (code "15") (name "LED_0") (class "Default")
      (node (ref "J1") (pin "1") (pinfunction "1_1") (pintype "unspecified"))
      (node (ref "R4") (pin "2") (pinfunction "2_2") (pintype "unspecified"))
      (node (ref "U1") (pin "66") (pinfunction "LED0/GPIO0/TDO/MNGT0_66") (pintype "unspecified"))
    )
    (net (code "16") (name "LED_3") (class "Default")
      (node (ref "J2") (pin "2") (pinfunction "2_2") (pintype "unspecified"))
      (node (ref "U1") (pin "47") (pinfunction "LED3/GPIO3/EEEEN_47") (pintype "unspecified"))
    )
    (net (code "17") (name "LED_5") (class "Default")
      (node (ref "J2") (pin "12") (pinfunction "12_12") (pintype "unspecified"))
      (node (ref "R10") (pin "2") (pinfunction "2_2") (pintype "unspecified"))
      (node (ref "U1") (pin "26") (pinfunction "LED5/GPIO5/PHYADD_26") (pintype "unspecified"))
    )
    (net (code "18") (name "Net-(J1-Pad2)") (class "Default")
      (node (ref "J1") (pin "2") (pinfunction "2_2") (pintype "unspecified"))
      (node (ref "R38") (pin "2") (pinfunction "2_2") (pintype "unspecified"))
    )
    (net (code "19") (name "Net-(J1-Pad12)") (class "Default")
      (node (ref "J1") (pin "12") (pinfunction "12_12") (pintype "unspecified"))
      (node (ref "R39") (pin "2") (pinfunction "2_2") (pintype "unspecified"))
    )
    (net (code "20") (name "Net-(J1-RCT)") (class "Default")
      (node (ref "C22") (pin "2") (pinfunction "2_2") (pintype "unspecified"))
      (node (ref "J1") (pin "4") (pinfunction "TCT_4") (pintype "unspecified"))
      (node (ref "J1") (pin "7") (pinfunction "RCT_7") (pintype "unspecified"))
      (node (ref "R40") (pin "1") (pinfunction "1_1") (pintype "unspecified"))
    )
    (net (code "21") (name "Net-(J2-Pad1)") (class "Default")
      (node (ref "J2") (pin "1") (pinfunction "1_1") (pintype "unspecified"))
      (node (ref "R50") (pin "2") (pinfunction "2_2") (pintype "unspecified"))
    )
    (net (code "22") (name "Net-(J2-Pad11)") (class "Default")
      (node (ref "J2") (pin "11") (pinfunction "11_11") (pintype "unspecified"))
      (node (ref "R51") (pin "2") (pinfunction "2_2") (pintype "unspecified"))
    )
    (net (code "23") (name "Net-(J2-RCT)") (class "Default")
      (node (ref "C23") (pin "2") (pinfunction "2_2") (pintype "unspecified"))
      (node (ref "J2") (pin "4") (pinfunction "TCT_4") (pintype "unspecified"))
      (node (ref "J2") (pin "7") (pinfunction "RCT_7") (pintype "unspecified"))
      (node (ref "R49") (pin "1") (pinfunction "1_1") (pintype "unspecified"))
    )
    (net (code "24") (name "Net-(U1-OSCI)") (class "Default")
      (node (ref "C6") (pin "2") (pinfunction "2_2") (pintype "unspecified"))
      (node (ref "U1") (pin "1") (pinfunction "OSCI_1") (pintype "unspecified"))
      (node (ref "X1") (pin "1") (pinfunction "XTAL_1_1") (pintype "unspecified"))
    )
    (net (code "25") (name "Net-(U1-OSCO)") (class "Default")
      (node (ref "C7") (pin "2") (pinfunction "2_2") (pintype "unspecified"))
      (node (ref "U1") (pin "2") (pinfunction "OSCO_2") (pintype "unspecified"))
      (node (ref "X1") (pin "3") (pinfunction "XTAL_2_3") (pintype "unspecified"))
    )
    (net (code "26") (name "Net-(U1-RBIAS)") (class "Default")
      (node (ref "R3") (pin "2") (pinfunction "2_2") (pintype "unspecified"))
      (node (ref "U1") (pin "80") (pinfunction "RBIAS_80") (pintype "unspecified"))
    )
    (net (code "27") (name "P0_CRS_DV") (class "Default")
      (node (ref "U1") (pin "34") (pinfunction "P0_OUTDV_34") (pintype "unspecified"))
      (node (ref "U2") (pin "1") (pinfunction "28_1") (pintype "unspecified"))
    )
    (net (code "28") (name "P0_IND1") (class "Default")
      (node (ref "U1") (pin "39") (pinfunction "P0_IND1_39") (pintype "unspecified"))
      (node (ref "U47") (pin "1") (pinfunction "44_1") (pintype "unspecified"))
    )
    (net (code "29") (name "P0_MDC") (class "Default")
      (node (ref "U1") (pin "57") (pinfunction "P0_MDC_57") (pintype "unspecified"))
      (node (ref "U26") (pin "1") (pinfunction "40_1") (pintype "unspecified"))
    )
    (net (code "30") (name "P0_MDIO") (class "Default")
      (node (ref "U1") (pin "58") (pinfunction "P0_MDIO_58") (pintype "unspecified"))
      (node (ref "U8") (pin "1") (pinfunction "34_1") (pintype "unspecified"))
    )
    (net (code "31") (name "P0_MODE0") (class "Default")
      (node (ref "R21") (pin "2") (pinfunction "2_2") (pintype "unspecified"))
      (node (ref "U1") (pin "36") (pinfunction "P0_OUTCLK/P0_REFCLK/P0_MODE0_36") (pintype "unspecified"))
      (node (ref "U20") (pin "1") (pinfunction "38_1") (pintype "unspecified"))
    )
    (net (code "32") (name "P0_MODE1") (class "Default")
      (node (ref "R20") (pin "1") (pinfunction "1_1") (pintype "unspecified"))
      (node (ref "U1") (pin "33") (pinfunction "P0_OUTD0/P0_MODE1_33") (pintype "unspecified"))
      (node (ref "U6") (pin "1") (pinfunction "32_1") (pintype "unspecified"))
    )
    (net (code "33") (name "P0_MODE2") (class "Default")
      (node (ref "R18") (pin "1") (pinfunction "1_1") (pintype "unspecified"))
      (node (ref "U1") (pin "32") (pinfunction "P0_OUTD1/P0_MODE2_32") (pintype "unspecified"))
      (node (ref "U4") (pin "1") (pinfunction "30_1") (pintype "unspecified"))
    )
    (net (code "34") (name "P0_MODE3") (class "Default")
      (node (ref "R15") (pin "1") (pinfunction "1_1") (pintype "unspecified"))
      (node (ref "U1") (pin "22") (pinfunction "P0_OUTD2/PO_MODE3_22") (pintype "unspecified"))
    )
    (net (code "35") (name "P0_TX_EN") (class "Default")
      (node (ref "U1") (pin "37") (pinfunction "P0_INDV_37") (pintype "unspecified"))
      (node (ref "U10") (pin "1") (pinfunction "36_1") (pintype "unspecified"))
    )
    (net (code "36") (name "P1_INTPHY") (class "Default")
      (node (ref "R25") (pin "1") (pinfunction "1_1") (pintype "unspecified"))
      (node (ref "U1") (pin "64") (pinfunction "LED1/GPIO/TDI/P1_INTPHY_64") (pintype "unspecified"))
    )
    (net (code "37") (name "P1_MODE0") (class "Default")
      (node (ref "R32") (pin "2") (pinfunction "2_2") (pintype "unspecified"))
      (node (ref "U1") (pin "50") (pinfunction "P1_OUTCLK/P1_REFCLK/P1_MODE0_50") (pintype "unspecified"))
    )
    (net (code "38") (name "P1_MODE1") (class "Default")
      (node (ref "R30") (pin "2") (pinfunction "2_2") (pintype "unspecified"))
      (node (ref "U1") (pin "52") (pinfunction "P1_OUTD0/P1_MODE1_52") (pintype "unspecified"))
    )
    (net (code "39") (name "P1_MODE2") (class "Default")
      (node (ref "R29") (pin "1") (pinfunction "1_1") (pintype "unspecified"))
      (node (ref "U1") (pin "51") (pinfunction "P1_OUTD1/P1_MODE2_51") (pintype "unspecified"))
    )
    (net (code "40") (name "P1_MODE3") (class "Default")
      (node (ref "R27") (pin "1") (pinfunction "1_1") (pintype "unspecified"))
      (node (ref "U1") (pin "49") (pinfunction "P1_OUTD2/P1_MODE3_49") (pintype "unspecified"))
    )
    (net (code "41") (name "R0_IND0") (class "Default")
      (node (ref "U1") (pin "38") (pinfunction "P0_IND0_38") (pintype "unspecified"))
      (node (ref "U76") (pin "1") (pinfunction "48_1") (pintype "unspecified"))
    )
    (net (code "42") (name "RX_A_N") (class "Default")
      (node (ref "C18") (pin "2") (pinfunction "2_2") (pintype "unspecified"))
      (node (ref "J1") (pin "8") (pinfunction "RD-_8") (pintype "unspecified"))
      (node (ref "R41") (pin "1") (pinfunction "1_1") (pintype "unspecified"))
      (node (ref "U1") (pin "77") (pinfunction "RXNA_77") (pintype "unspecified"))
    )
    (net (code "43") (name "RX_A_P") (class "Default")
      (node (ref "C19") (pin "2") (pinfunction "2_2") (pintype "unspecified"))
      (node (ref "J1") (pin "6") (pinfunction "RD+_6") (pintype "unspecified"))
      (node (ref "R42") (pin "1") (pinfunction "1_1") (pintype "unspecified"))
      (node (ref "U1") (pin "78") (pinfunction "RXPA_78") (pintype "unspecified"))
    )
    (net (code "44") (name "RX_B_N") (class "Default")
      (node (ref "C27") (pin "2") (pinfunction "2_2") (pintype "unspecified"))
      (node (ref "J2") (pin "8") (pinfunction "RD-_8") (pintype "unspecified"))
      (node (ref "R48") (pin "1") (pinfunction "1_1") (pintype "unspecified"))
      (node (ref "U1") (pin "84") (pinfunction "RXNB_84") (pintype "unspecified"))
    )
    (net (code "45") (name "RX_B_P") (class "Default")
      (node (ref "C26") (pin "2") (pinfunction "2_2") (pintype "unspecified"))
      (node (ref "J2") (pin "6") (pinfunction "RD+_6") (pintype "unspecified"))
      (node (ref "R47") (pin "1") (pinfunction "1_1") (pintype "unspecified"))
      (node (ref "U1") (pin "83") (pinfunction "RXPB_83") (pintype "unspecified"))
    )
    (net (code "46") (name "TX_A_N") (class "Default")
      (node (ref "C20") (pin "2") (pinfunction "2_2") (pintype "unspecified"))
      (node (ref "J1") (pin "5") (pinfunction "TD-_5") (pintype "unspecified"))
      (node (ref "R43") (pin "1") (pinfunction "1_1") (pintype "unspecified"))
      (node (ref "U1") (pin "75") (pinfunction "TXNA_75") (pintype "unspecified"))
    )
    (net (code "47") (name "TX_A_P") (class "Default")
      (node (ref "C21") (pin "2") (pinfunction "2_2") (pintype "unspecified"))
      (node (ref "J1") (pin "3") (pinfunction "TD+_3") (pintype "unspecified"))
      (node (ref "R44") (pin "1") (pinfunction "1_1") (pintype "unspecified"))
      (node (ref "U1") (pin "76") (pinfunction "TXPA_76") (pintype "unspecified"))
    )
    (net (code "48") (name "TX_B_N") (class "Default")
      (node (ref "C25") (pin "2") (pinfunction "2_2") (pintype "unspecified"))
      (node (ref "J2") (pin "5") (pinfunction "TD-_5") (pintype "unspecified"))
      (node (ref "R46") (pin "1") (pinfunction "1_1") (pintype "unspecified"))
      (node (ref "U1") (pin "86") (pinfunction "TXNB_86") (pintype "unspecified"))
    )
    (net (code "49") (name "TX_B_P") (class "Default")
      (node (ref "C24") (pin "2") (pinfunction "2_2") (pintype "unspecified"))
      (node (ref "J2") (pin "3") (pinfunction "TD+_3") (pintype "unspecified"))
      (node (ref "R45") (pin "1") (pinfunction "1_1") (pintype "unspecified"))
      (node (ref "U1") (pin "85") (pinfunction "TXPB_85") (pintype "unspecified"))
    )
    (net (code "50") (name "unconnected-(U1-GPIO6-Pad14)") (class "Default")
      (node (ref "U1") (pin "14") (pinfunction "GPIO6_14") (pintype "unspecified+no_connect"))
    )
    (net (code "51") (name "unconnected-(U1-GPIO7-Pad13)") (class "Default")
      (node (ref "U1") (pin "13") (pinfunction "GPIO7_13") (pintype "unspecified+no_connect"))
    )
    (net (code "52") (name "unconnected-(U1-I2CSCL{slash}EESCL{slash}TCK-Pad61)") (class "Default")
      (node (ref "U1") (pin "61") (pinfunction "I2CSCL/EESCL/TCK_61") (pintype "unspecified+no_connect"))
    )
    (net (code "53") (name "unconnected-(U1-I2CSDA{slash}EESDA{slash}TMS-Pad60)") (class "Default")
      (node (ref "U1") (pin "60") (pinfunction "I2CSDA/EESDA/TMS_60") (pintype "unspecified+no_connect"))
    )
    (net (code "54") (name "unconnected-(U1-LED4{slash}GPIO4{slash}1588EN-Pad27)") (class "Default")
      (node (ref "U1") (pin "27") (pinfunction "LED4/GPIO4/1588EN_27") (pintype "unspecified+no_connect"))
    )
    (net (code "55") (name "unconnected-(U1-NC-Pad11)") (class "Default")
      (node (ref "U1") (pin "11") (pinfunction "NC_11") (pintype "unspecified+no_connect"))
    )
    (net (code "56") (name "unconnected-(U1-NC-Pad18)") (class "Default")
      (node (ref "U1") (pin "18") (pinfunction "NC_18") (pintype "unspecified+no_connect"))
    )
    (net (code "57") (name "unconnected-(U1-NC-Pad29)") (class "Default")
      (node (ref "U1") (pin "29") (pinfunction "NC_29") (pintype "unspecified+no_connect"))
    )
    (net (code "58") (name "unconnected-(U1-NC-Pad31)") (class "Default")
      (node (ref "U1") (pin "31") (pinfunction "NC_31") (pintype "unspecified+no_connect"))
    )
    (net (code "59") (name "unconnected-(U1-NC-Pad45)") (class "Default")
      (node (ref "U1") (pin "45") (pinfunction "NC_45") (pintype "unspecified+no_connect"))
    )
    (net (code "60") (name "unconnected-(U1-NC-Pad67)") (class "Default")
      (node (ref "U1") (pin "67") (pinfunction "NC_67") (pintype "unspecified+no_connect"))
    )
    (net (code "61") (name "unconnected-(U1-NC-Pad68)") (class "Default")
      (node (ref "U1") (pin "68") (pinfunction "NC_68") (pintype "unspecified+no_connect"))
    )
    (net (code "62") (name "unconnected-(U1-NC-Pad88)") (class "Default")
      (node (ref "U1") (pin "88") (pinfunction "NC_88") (pintype "unspecified+no_connect"))
    )
    (net (code "63") (name "unconnected-(U1-OSCVDD12-Pad3)") (class "Default")
      (node (ref "U1") (pin "3") (pinfunction "OSCVDD12_3") (pintype "unspecified+no_connect"))
    )
    (net (code "64") (name "unconnected-(U1-P0_COL-Pad70)") (class "Default")
      (node (ref "U1") (pin "70") (pinfunction "P0_COL_70") (pintype "unspecified+no_connect"))
    )
    (net (code "65") (name "unconnected-(U1-P0_CRS-Pad69)") (class "Default")
      (node (ref "U1") (pin "69") (pinfunction "P0_CRS_69") (pintype "unspecified+no_connect"))
    )
    (net (code "66") (name "unconnected-(U1-P0_DUPLEX-Pad54)") (class "Default")
      (node (ref "U1") (pin "54") (pinfunction "P0_DUPLEX_54") (pintype "unspecified+no_connect"))
    )
    (net (code "67") (name "unconnected-(U1-P0_INCLK-Pad40)") (class "Default")
      (node (ref "U1") (pin "40") (pinfunction "P0_INCLK_40") (pintype "unspecified+no_connect"))
    )
    (net (code "68") (name "unconnected-(U1-P0_IND2-Pad41)") (class "Default")
      (node (ref "U1") (pin "41") (pinfunction "P0_IND2_41") (pintype "unspecified+no_connect"))
    )
    (net (code "69") (name "unconnected-(U1-P0_IND3-Pad42)") (class "Default")
      (node (ref "U1") (pin "42") (pinfunction "P0_IND3_42") (pintype "unspecified+no_connect"))
    )
    (net (code "70") (name "unconnected-(U1-P0_INER-Pad46)") (class "Default")
      (node (ref "U1") (pin "46") (pinfunction "P0_INER_46") (pintype "unspecified+no_connect"))
    )
    (net (code "71") (name "unconnected-(U1-P0_OUTD3-Pad21)") (class "Default")
      (node (ref "U1") (pin "21") (pinfunction "P0_OUTD3_21") (pintype "unspecified+no_connect"))
    )
    (net (code "72") (name "unconnected-(U1-P0_OUTER{slash}P0_SPEED-Pad28)") (class "Default")
      (node (ref "U1") (pin "28") (pinfunction "P0_OUTER/P0_SPEED_28") (pintype "unspecified+no_connect"))
    )
    (net (code "73") (name "unconnected-(U1-P1_COL-Pad72)") (class "Default")
      (node (ref "U1") (pin "72") (pinfunction "P1_COL_72") (pintype "unspecified+no_connect"))
    )
    (net (code "74") (name "unconnected-(U1-P1_CRS-Pad73)") (class "Default")
      (node (ref "U1") (pin "73") (pinfunction "P1_CRS_73") (pintype "unspecified+no_connect"))
    )
    (net (code "75") (name "unconnected-(U1-P1_DUPLEX{slash}P1_MDC-Pad71)") (class "Default")
      (node (ref "U1") (pin "71") (pinfunction "P1_DUPLEX/P1_MDC_71") (pintype "unspecified+no_connect"))
    )
    (net (code "76") (name "unconnected-(U1-P1_INCLK-Pad20)") (class "Default")
      (node (ref "U1") (pin "20") (pinfunction "P1_INCLK_20") (pintype "unspecified+no_connect"))
    )
    (net (code "77") (name "unconnected-(U1-P1_IND0-Pad24)") (class "Default")
      (node (ref "U1") (pin "24") (pinfunction "P1_IND0_24") (pintype "unspecified+no_connect"))
    )
    (net (code "78") (name "unconnected-(U1-P1_IND1-Pad23)") (class "Default")
      (node (ref "U1") (pin "23") (pinfunction "P1_IND1_23") (pintype "unspecified+no_connect"))
    )
    (net (code "79") (name "unconnected-(U1-P1_IND2-Pad16)") (class "Default")
      (node (ref "U1") (pin "16") (pinfunction "P1_IND2_16") (pintype "unspecified+no_connect"))
    )
    (net (code "80") (name "unconnected-(U1-P1_IND3-Pad15)") (class "Default")
      (node (ref "U1") (pin "15") (pinfunction "P1_IND3_15") (pintype "unspecified+no_connect"))
    )
    (net (code "81") (name "unconnected-(U1-P1_INDV-Pad25)") (class "Default")
      (node (ref "U1") (pin "25") (pinfunction "P1_INDV_25") (pintype "unspecified+no_connect"))
    )
    (net (code "82") (name "unconnected-(U1-P1_INER-Pad19)") (class "Default")
      (node (ref "U1") (pin "19") (pinfunction "P1_INER_19") (pintype "unspecified+no_connect"))
    )
    (net (code "83") (name "unconnected-(U1-P1_OUTD3-Pad48)") (class "Default")
      (node (ref "U1") (pin "48") (pinfunction "P1_OUTD3_48") (pintype "unspecified+no_connect"))
    )
    (net (code "84") (name "unconnected-(U1-P1_OUTDV-Pad53)") (class "Default")
      (node (ref "U1") (pin "53") (pinfunction "P1_OUTDV_53") (pintype "unspecified+no_connect"))
    )
    (net (code "85") (name "unconnected-(U1-P1_OUTER{slash}P1_SPEED{slash}P1_MDIO-Pad44)") (class "Default")
      (node (ref "U1") (pin "44") (pinfunction "P1_OUTER/P1_SPEED/P1_MDIO_44") (pintype "unspecified+no_connect"))
    )
  )
)
